# ch347f.net
KiCad netlist of a schematic drawn in Altium Designer
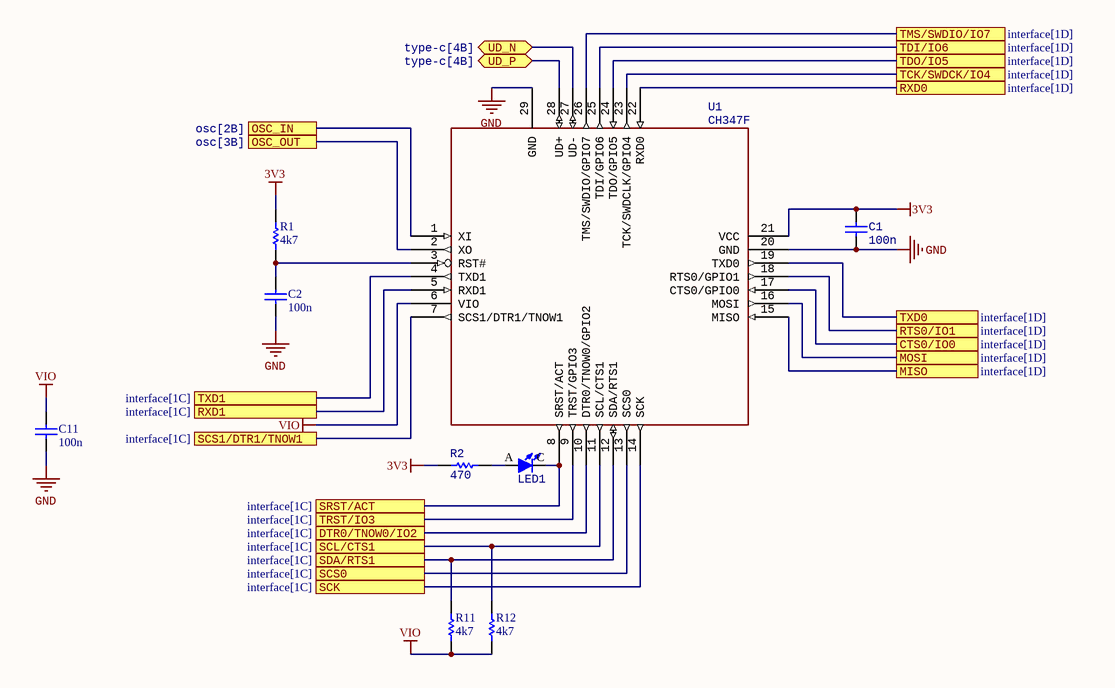
[diagram p0: ch347f.SchDoc]

(export (version "E")
  (design (tool "Eeschema 10.0.6"))
  (components
    (comp (ref "C1")
      (value "100n")
      (footprint "CAPC100X50X55L25N")
      (fields
        (field (name "MPN") "TCC0402X5R104M250AT")
        (field (name "MANUFACTURER") "CCTC(三环)")
        (field (name "Comment") "Capacitor")
      )
      (libsource (lib "std_lib") (part "Capacitor"))
    )
    (comp (ref "C2")
      (value "100n")
      (footprint "CAPC100X50X55L25N")
      (fields
        (field (name "MPN") "TCC0402X5R104M250AT")
        (field (name "MANUFACTURER") "CCTC(三环)")
        (field (name "Comment") "Capacitor")
      )
      (libsource (lib "std_lib") (part "Capacitor"))
    )
    (comp (ref "C11")
      (value "100n")
      (footprint "CAPC100X50X55L25N")
      (fields
        (field (name "MPN") "TCC0402X5R104M250AT")
        (field (name "MANUFACTURER") "CCTC(三环)")
        (field (name "Comment") "Capacitor")
      )
      (libsource (lib "std_lib") (part "Capacitor"))
    )
    (comp (ref "LED1")
      (value "蓝灯 正贴")
      (footprint "footprints:LEDC100X50X45L25N")
      (description "贴片LED")
      (libsource (lib "mcontroller") (part "LED-SMD"))
    )
    (comp (ref "R1")
      (value "4k7")
      (footprint "RESC100X50X35L25N")
      (fields
        (field (name "MPN") "RTT02472JTH")
        (field (name "MANUFACTURER") "RALEC(旺诠)")
        (field (name "Comment") "Resistor")
      )
      (libsource (lib "std_lib") (part "Resistor"))
    )
    (comp (ref "R2")
      (value "470")
      (footprint "RESC100X50X35L25N")
      (fields
        (field (name "MPN") "RTT02471JTH")
        (field (name "MANUFACTURER") "RALEC(旺诠)")
        (field (name "Comment") "Resistor")
      )
      (libsource (lib "std_lib") (part "Resistor"))
    )
    (comp (ref "R11")
      (value "4k7")
      (footprint "RESC100X50X35L25N")
      (fields
        (field (name "MPN") "RTT02472JTH")
        (field (name "MANUFACTURER") "RALEC(旺诠)")
        (field (name "Comment") "Resistor")
      )
      (libsource (lib "std_lib") (part "Resistor"))
    )
    (comp (ref "R12")
      (value "4k7")
      (footprint "RESC100X50X35L25N")
      (fields
        (field (name "MPN") "RTT02472JTH")
        (field (name "MANUFACTURER") "RALEC(旺诠)")
        (field (name "Comment") "Resistor")
      )
      (libsource (lib "std_lib") (part "Resistor"))
    )
    (comp (ref "U1")
      (value "CH347F")
      (footprint "ch347-hs-usb-bridge:QFN-28_L4.0-W4.0-P0.40-BL-EP2.7")
      (description "High Speed USB to UART + SPI + IIC + JTAG")
      (libsource (lib "Sch") (part "CH347F"))
    )
  )
  (nets
    (net (code "1") (name "/CTS0{slash}IO0") (class "Default")
      (node (ref "U1") (pin "17") (pinfunction "CTS0/GPIO0_17") (pintype "input"))
    )
    (net (code "2") (name "/DTR0{slash}TNOW0{slash}IO2") (class "Default")
      (node (ref "U1") (pin "10") (pinfunction "DTR0/TNOW0/GPIO2_10") (pintype "output"))
    )
    (net (code "3") (name "/MISO") (class "Default")
      (node (ref "U1") (pin "15") (pinfunction "MISO_15") (pintype "input"))
    )
    (net (code "4") (name "/MOSI") (class "Default")
      (node (ref "U1") (pin "16") (pinfunction "MOSI_16") (pintype "output"))
    )
    (net (code "5") (name "/OSC_IN") (class "Default")
      (node (ref "U1") (pin "1") (pinfunction "XI_1") (pintype "input"))
    )
    (net (code "6") (name "/OSC_OUT") (class "Default")
      (node (ref "U1") (pin "2") (pinfunction "XO_2") (pintype "output"))
    )
    (net (code "7") (name "/RTS0{slash}IO1") (class "Default")
      (node (ref "U1") (pin "18") (pinfunction "RTS0/GPIO1_18") (pintype "output"))
    )
    (net (code "8") (name "/RXD0") (class "Default")
      (node (ref "U1") (pin "22") (pinfunction "RXD0_22") (pintype "input"))
    )
    (net (code "9") (name "/RXD1") (class "Default")
      (node (ref "U1") (pin "5") (pinfunction "RXD1_5") (pintype "input"))
    )
    (net (code "10") (name "/SCK") (class "Default")
      (node (ref "U1") (pin "14") (pinfunction "SCK_14") (pintype "output"))
    )
    (net (code "11") (name "/SCL{slash}CTS1") (class "Default")
      (node (ref "R12") (pin "1") (pinfunction "1_1") (pintype "passive"))
      (node (ref "U1") (pin "11") (pinfunction "SCL/CTS1_11") (pintype "output"))
    )
    (net (code "12") (name "/SCS0") (class "Default")
      (node (ref "U1") (pin "13") (pinfunction "SCS0_13") (pintype "output"))
    )
    (net (code "13") (name "/SCS1{slash}DTR1{slash}TNOW1") (class "Default")
      (node (ref "U1") (pin "7") (pinfunction "SCS1/DTR1/TNOW1_7") (pintype "output"))
    )
    (net (code "14") (name "/SDA{slash}RTS1") (class "Default")
      (node (ref "R11") (pin "1") (pinfunction "1_1") (pintype "passive"))
      (node (ref "U1") (pin "12") (pinfunction "SDA/RTS1_12") (pintype "bidirectional"))
    )
    (net (code "15") (name "/SRST{slash}ACT") (class "Default")
      (node (ref "LED1") (pin "C") (pinfunction "K_C") (pintype "passive"))
      (node (ref "U1") (pin "8") (pinfunction "SRST/ACT_8") (pintype "output"))
    )
    (net (code "16") (name "/TCK{slash}SWDCK{slash}IO4") (class "Default")
      (node (ref "U1") (pin "23") (pinfunction "TCK/SWDCLK/GPIO4_23") (pintype "output"))
    )
    (net (code "17") (name "/TDI{slash}IO6") (class "Default")
      (node (ref "U1") (pin "25") (pinfunction "TDI/GPIO6_25") (pintype "output"))
    )
    (net (code "18") (name "/TDO{slash}IO5") (class "Default")
      (node (ref "U1") (pin "24") (pinfunction "TDO/GPIO5_24") (pintype "input"))
    )
    (net (code "19") (name "/TMS{slash}SWDIO{slash}IO7") (class "Default")
      (node (ref "U1") (pin "26") (pinfunction "TMS/SWDIO/GPIO7_26") (pintype "output"))
    )
    (net (code "20") (name "/TRST{slash}IO3") (class "Default")
      (node (ref "U1") (pin "9") (pinfunction "TRST/GPIO3_9") (pintype "output"))
    )
    (net (code "21") (name "/TXD0") (class "Default")
      (node (ref "U1") (pin "19") (pinfunction "TXD0_19") (pintype "output"))
    )
    (net (code "22") (name "/TXD1") (class "Default")
      (node (ref "U1") (pin "4") (pinfunction "TXD1_4") (pintype "output"))
    )
    (net (code "23") (name "/UD_N") (class "Default")
      (node (ref "U1") (pin "27") (pinfunction "UD-_27") (pintype "bidirectional"))
    )
    (net (code "24") (name "/UD_P") (class "Default")
      (node (ref "U1") (pin "28") (pinfunction "UD+_28") (pintype "bidirectional"))
    )
    (net (code "25") (name "3V3") (class "Default")
      (node (ref "C1") (pin "2") (pinfunction "2_2") (pintype "passive"))
      (node (ref "R1") (pin "1") (pinfunction "1_1") (pintype "passive"))
      (node (ref "R2") (pin "1") (pinfunction "1_1") (pintype "passive"))
      (node (ref "U1") (pin "21") (pinfunction "VCC_21") (pintype "power_in"))
    )
    (net (code "26") (name "GND") (class "Default")
      (node (ref "C1") (pin "1") (pinfunction "1_1") (pintype "passive"))
      (node (ref "C11") (pin "1") (pinfunction "1_1") (pintype "passive"))
      (node (ref "C2") (pin "1") (pinfunction "1_1") (pintype "passive"))
      (node (ref "U1") (pin "20") (pinfunction "GND_20") (pintype "power_in"))
      (node (ref "U1") (pin "29") (pinfunction "GND_29") (pintype "power_in"))
    )
    (net (code "27") (name "Net-(LED1-PadA)") (class "Default")
      (node (ref "LED1") (pin "A") (pinfunction "A_A") (pintype "passive"))
      (node (ref "R2") (pin "2") (pinfunction "2_2") (pintype "passive"))
    )
    (net (code "28") (name "Net-(U1-RST#)") (class "Default")
      (node (ref "C2") (pin "2") (pinfunction "2_2") (pintype "passive"))
      (node (ref "R1") (pin "2") (pinfunction "2_2") (pintype "passive"))
      (node (ref "U1") (pin "3") (pinfunction "RST#_3") (pintype "input"))
    )
    (net (code "29") (name "VIO") (class "Default")
      (node (ref "C11") (pin "2") (pinfunction "2_2") (pintype "passive"))
      (node (ref "R11") (pin "2") (pinfunction "2_2") (pintype "passive"))
      (node (ref "R12") (pin "2") (pinfunction "2_2") (pintype "passive"))
      (node (ref "U1") (pin "6") (pinfunction "VIO_6") (pintype "power_in"))
    )
  )
)
